# LAUNCHXL-F28069_B_1400922.net
KiCad netlist of a schematic drawn in EAGLE
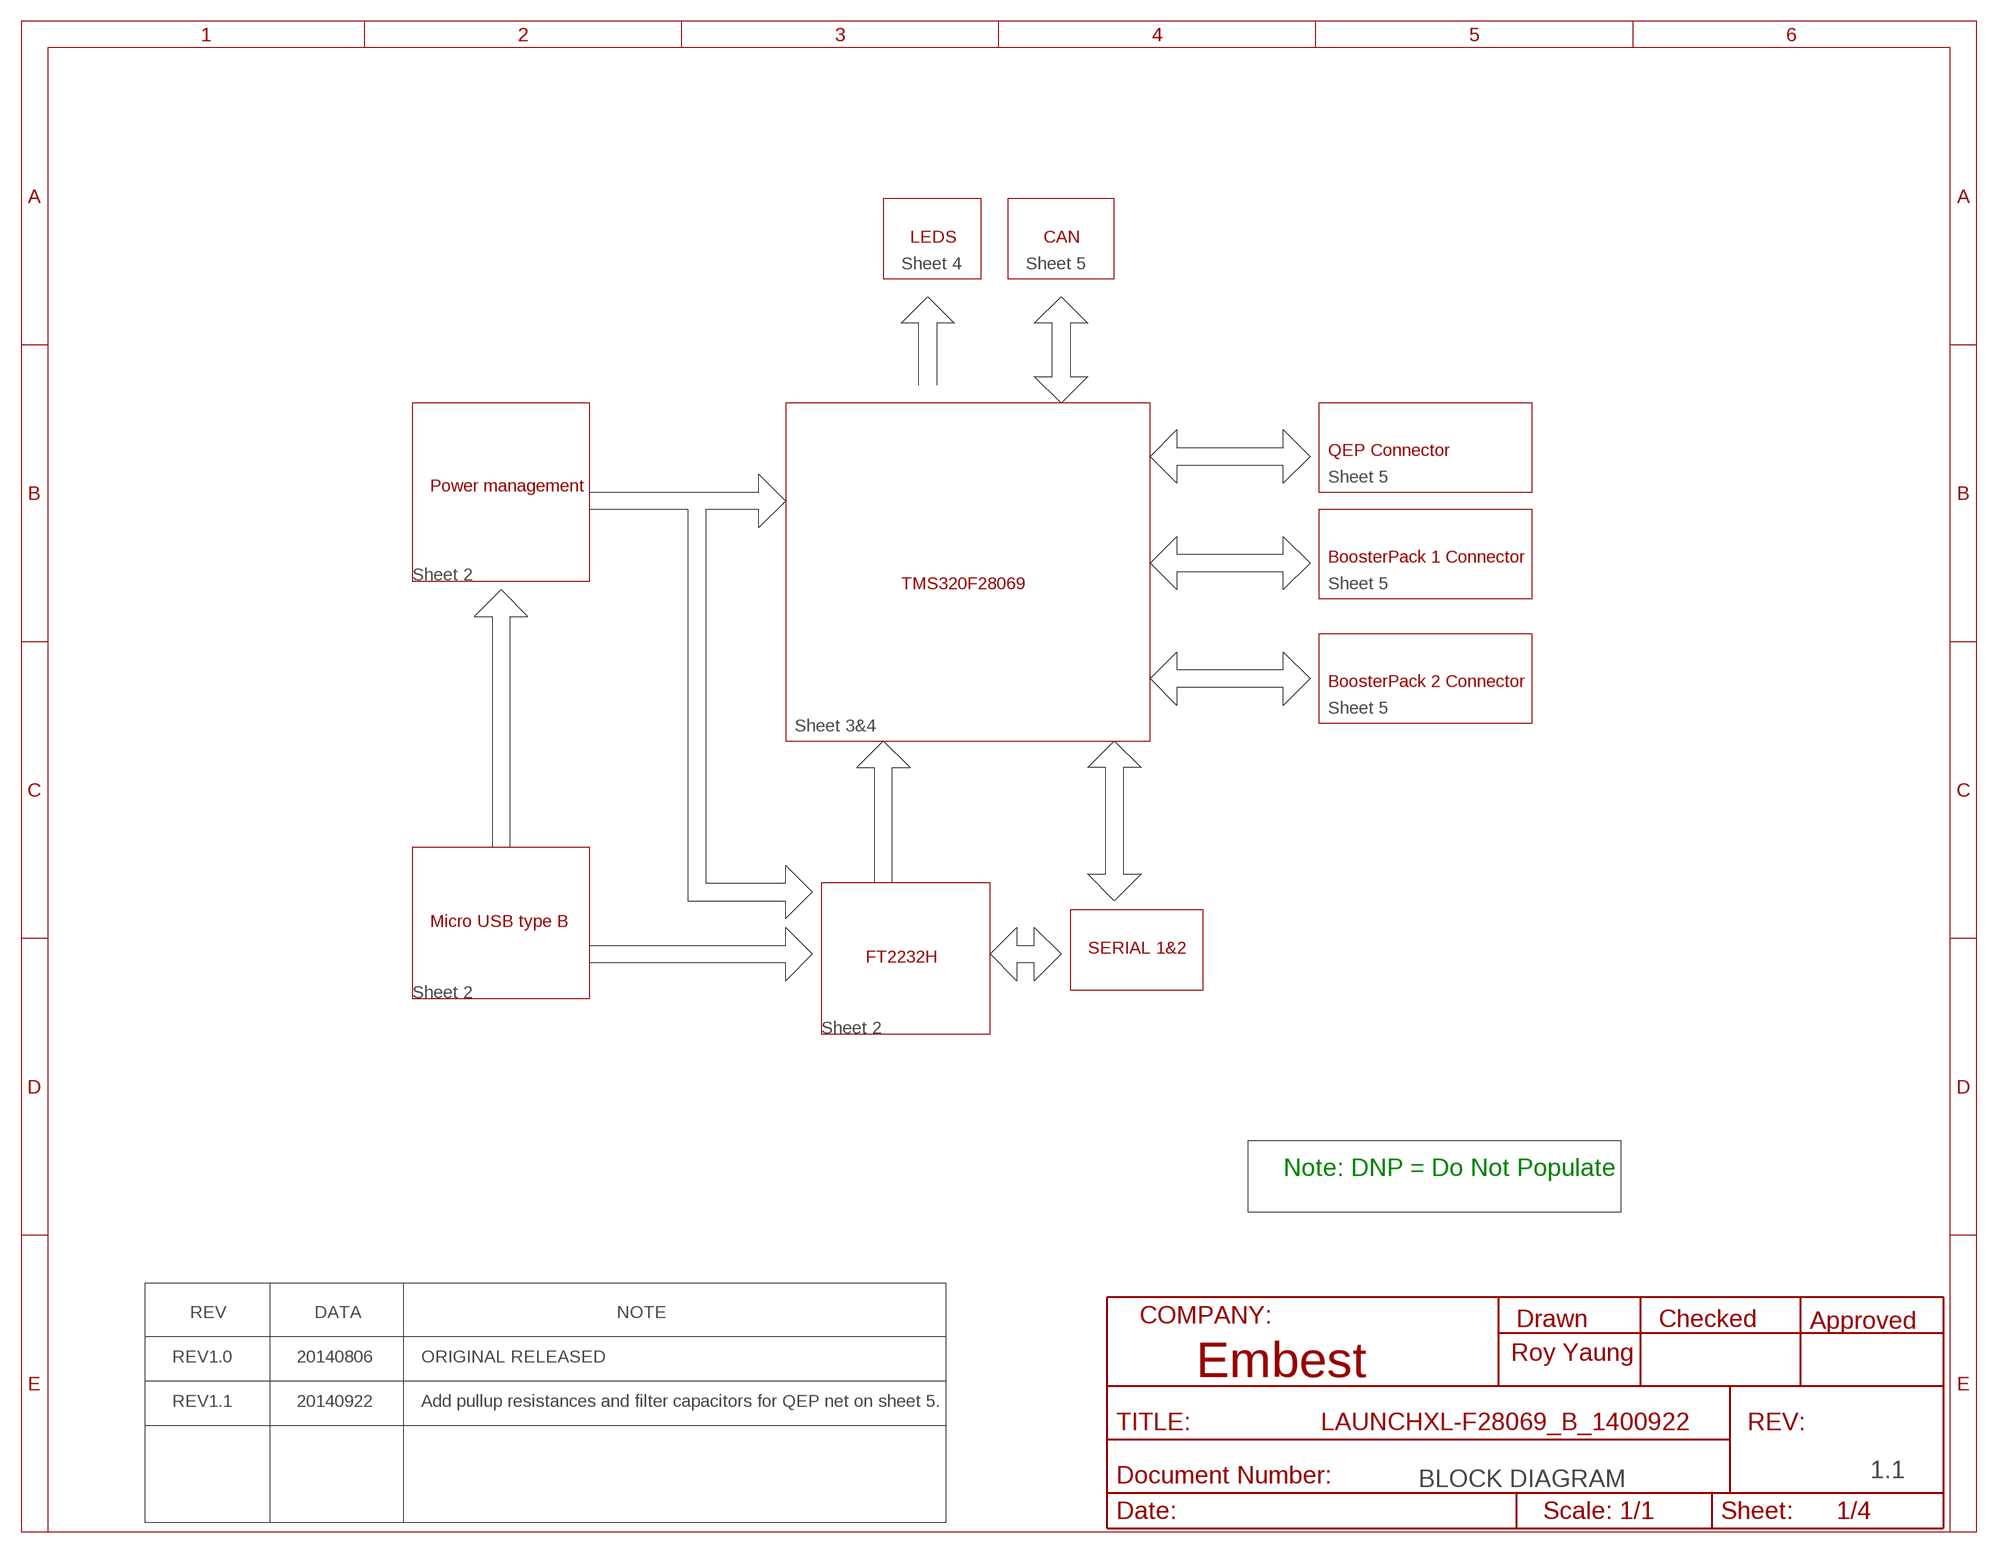
[diagram p0: schematic, sheet 1]
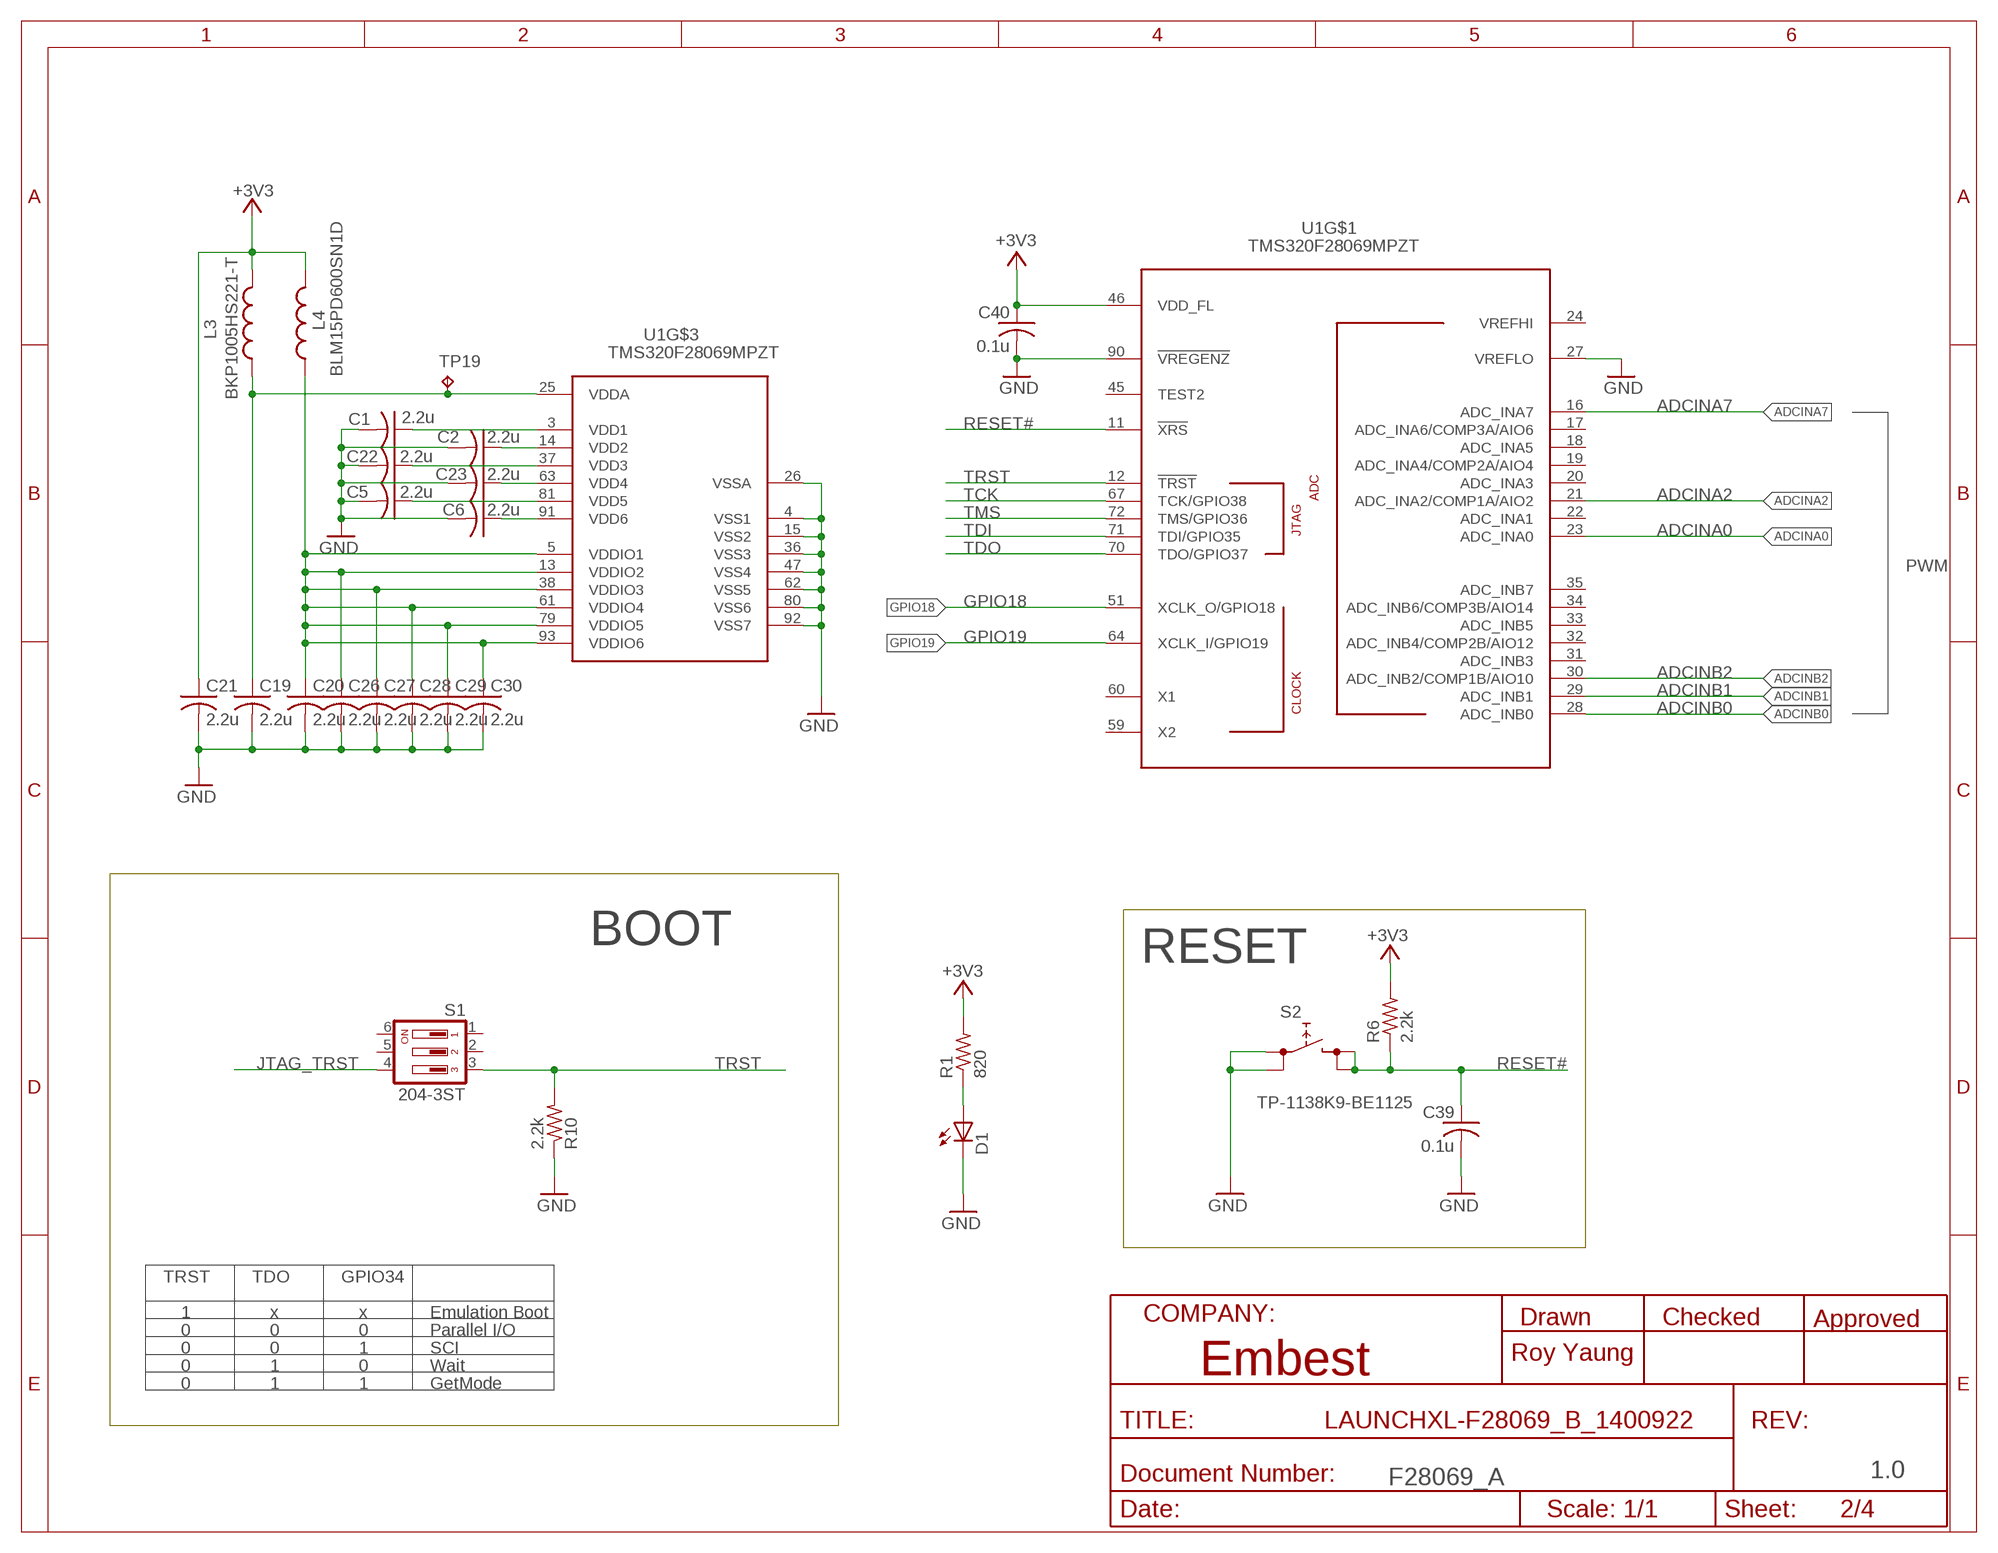
[diagram p1: schematic, sheet 2]
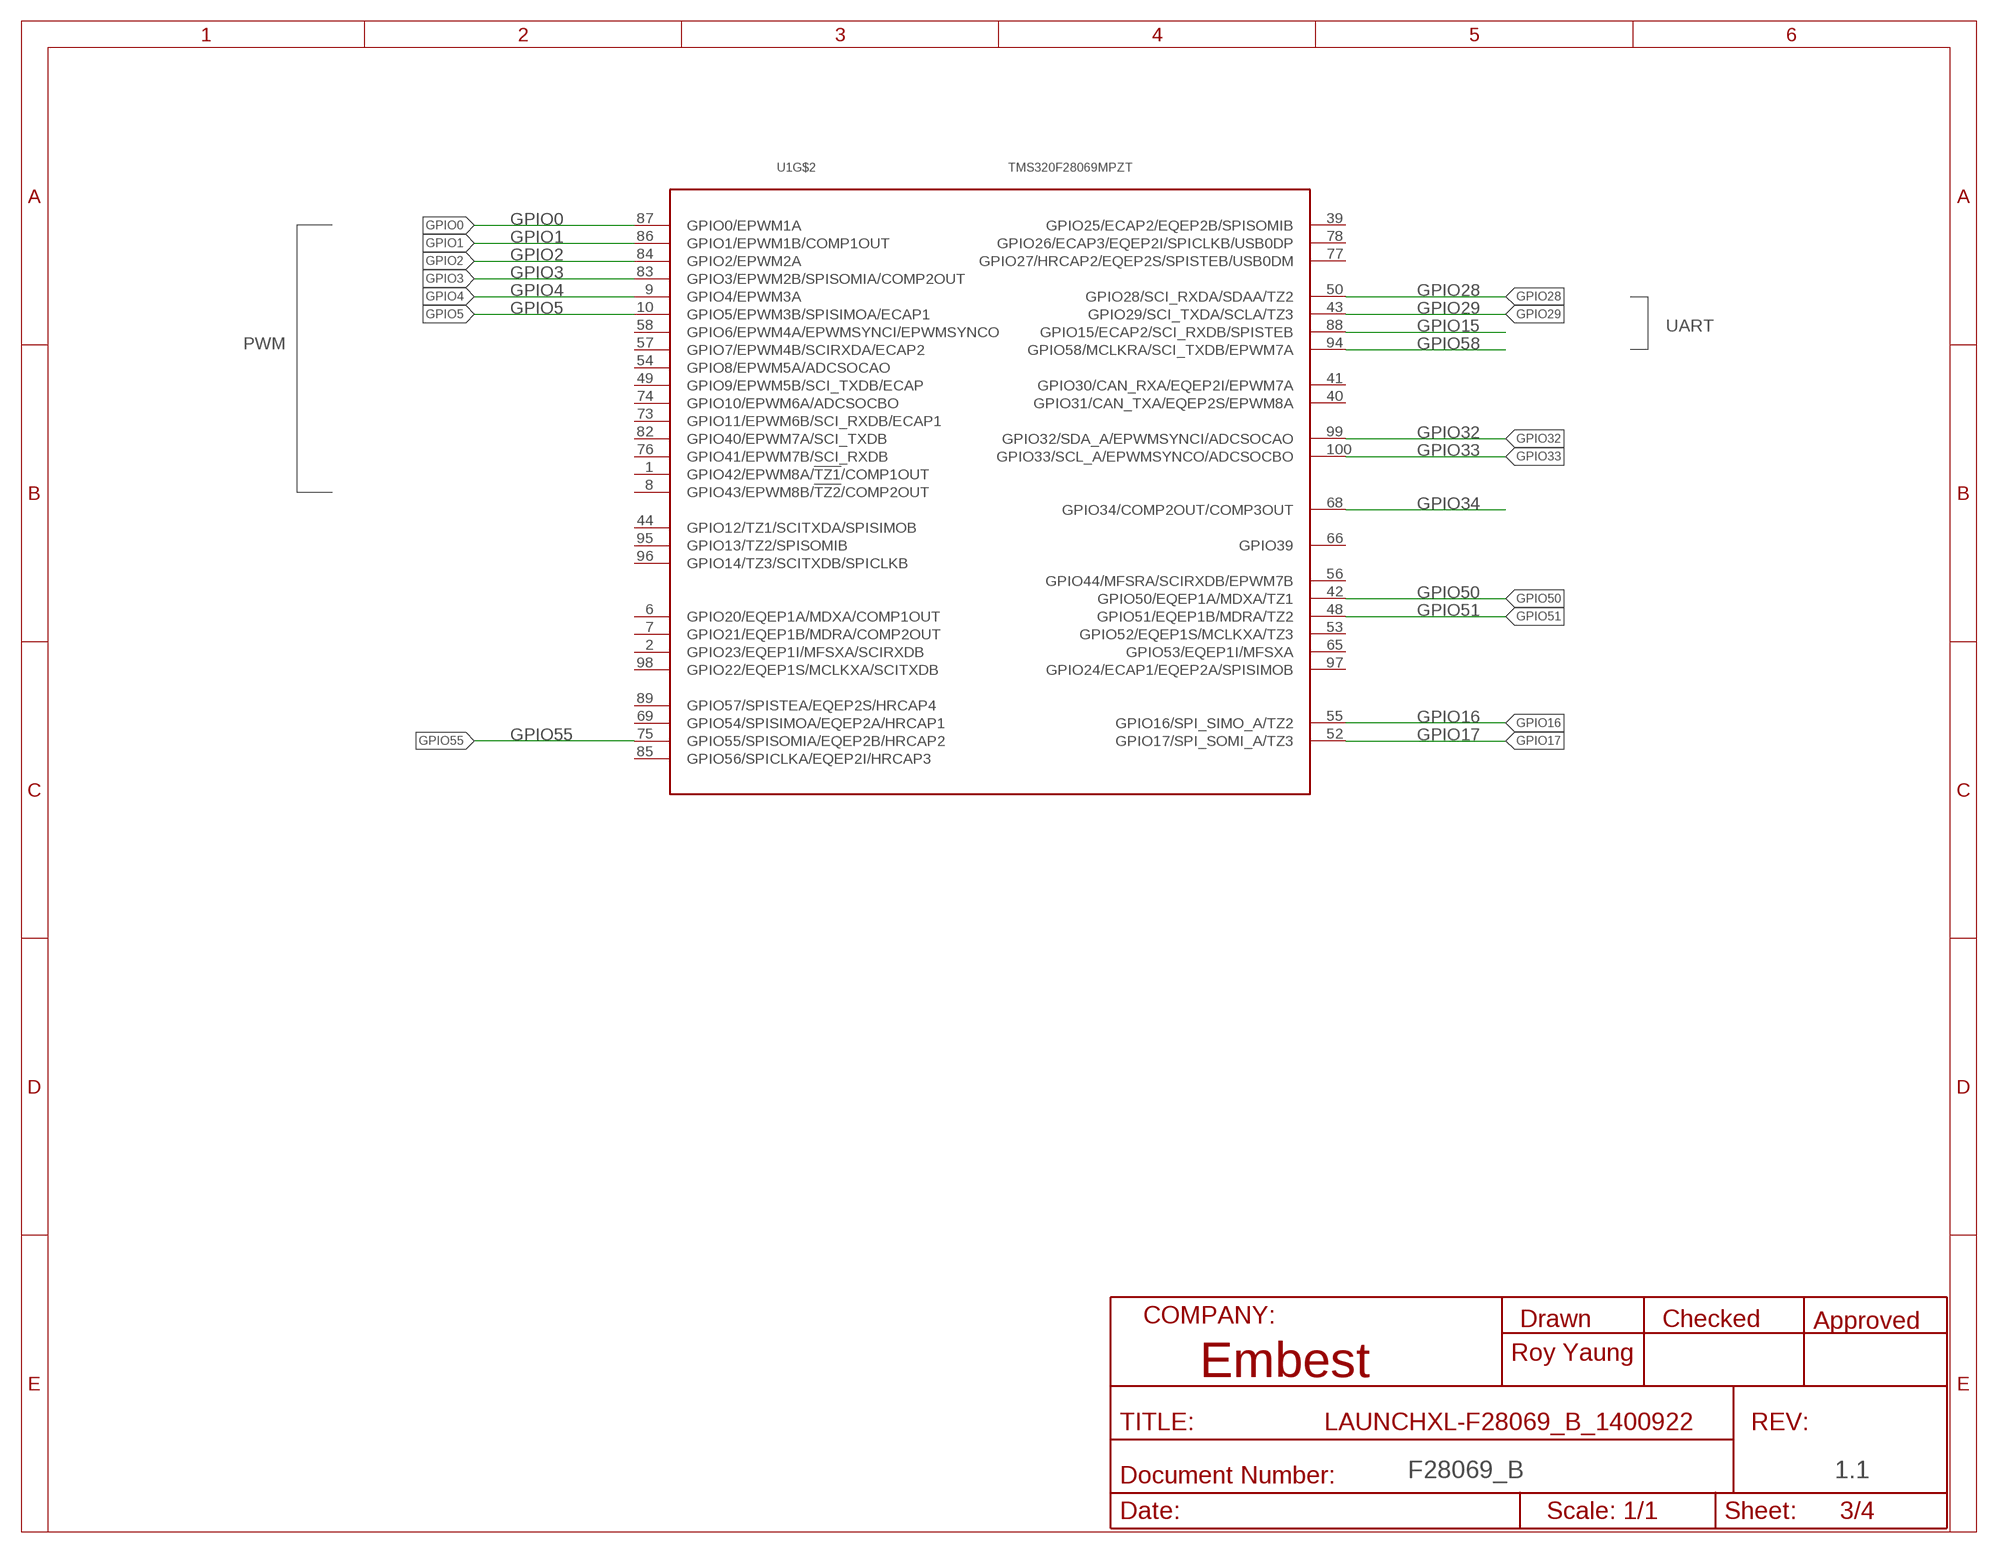
[diagram p2: schematic, sheet 3]
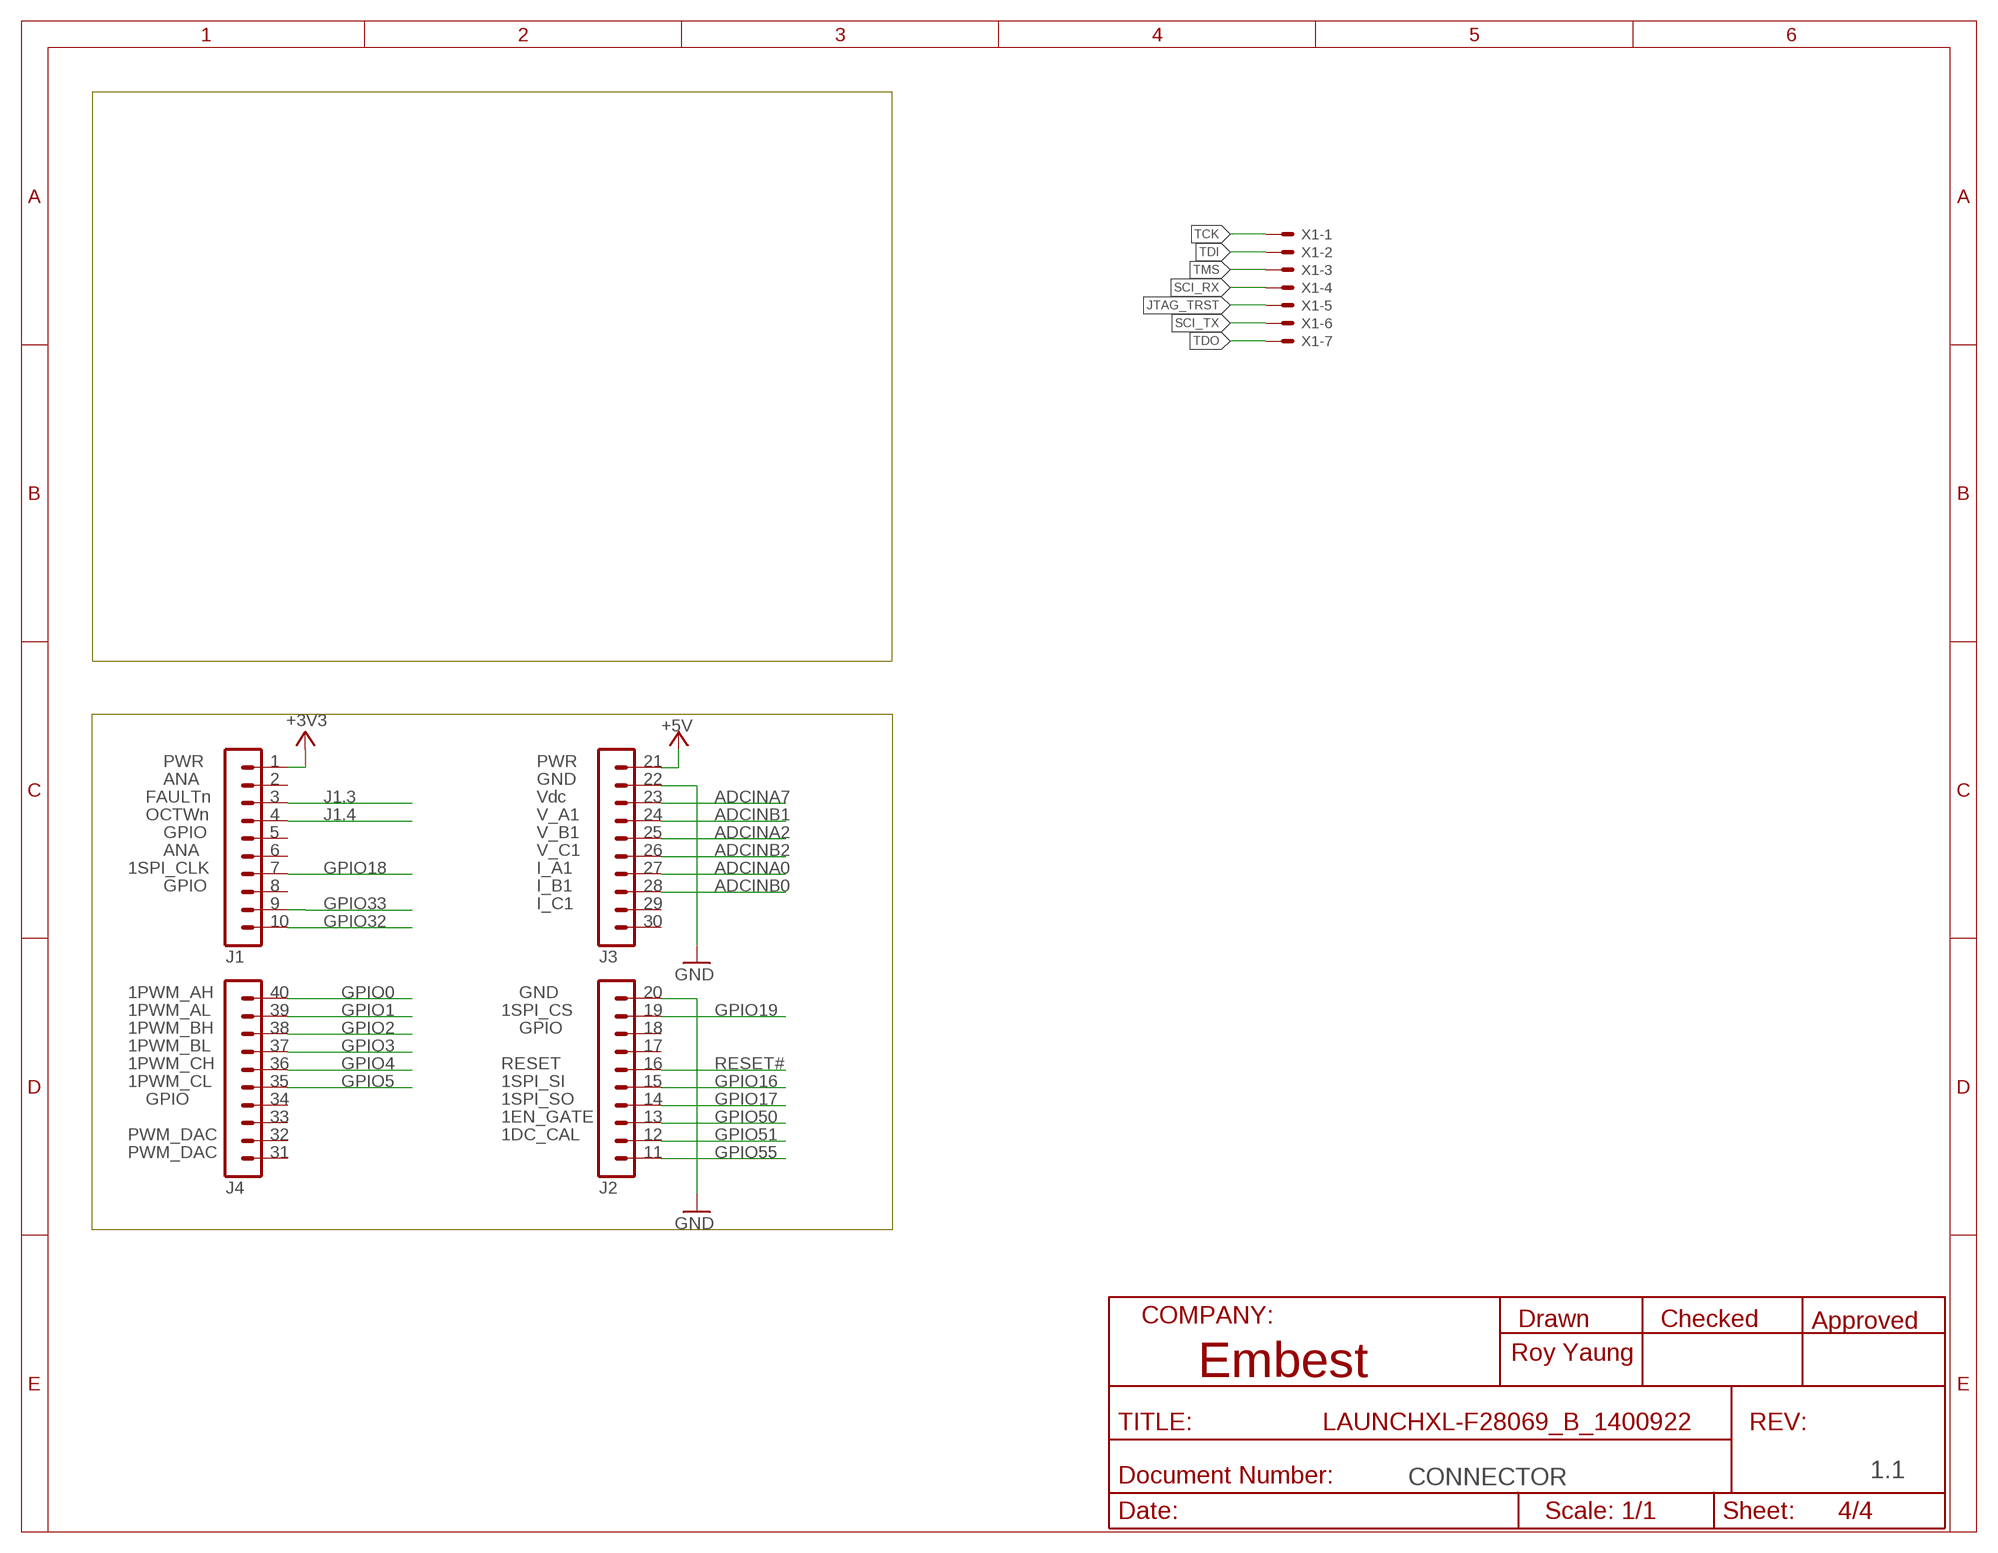
[diagram p3: schematic, sheet 4]

(export (version "E")
  (design (tool "Eeschema 10.0.6"))
  (components
    (comp (ref "C1")
      (value "2.2u")
      (footprint "eagle-import:C0402")
      (libsource (lib "eagle-import") (part "C-USC0402"))
    )
    (comp (ref "C2")
      (value "2.2u")
      (footprint "eagle-import:C0402")
      (libsource (lib "eagle-import") (part "C-USC0402"))
    )
    (comp (ref "C5")
      (value "2.2u")
      (footprint "eagle-import:C0402")
      (libsource (lib "eagle-import") (part "C-USC0402"))
    )
    (comp (ref "C6")
      (value "2.2u")
      (footprint "eagle-import:C0402")
      (libsource (lib "eagle-import") (part "C-USC0402"))
    )
    (comp (ref "C19")
      (value "2.2u")
      (footprint "eagle-import:C0402")
      (libsource (lib "eagle-import") (part "C-USC0402"))
    )
    (comp (ref "C20")
      (value "2.2u")
      (footprint "eagle-import:C0402")
      (libsource (lib "eagle-import") (part "C-USC0402"))
    )
    (comp (ref "C21")
      (value "2.2u")
      (footprint "eagle-import:C0402")
      (libsource (lib "eagle-import") (part "C-USC0402"))
    )
    (comp (ref "C22")
      (value "2.2u")
      (footprint "eagle-import:C0402")
      (libsource (lib "eagle-import") (part "C-USC0402"))
    )
    (comp (ref "C23")
      (value "2.2u")
      (footprint "eagle-import:C0402")
      (libsource (lib "eagle-import") (part "C-USC0402"))
    )
    (comp (ref "C26")
      (value "2.2u")
      (footprint "eagle-import:C0402")
      (libsource (lib "eagle-import") (part "C-USC0402"))
    )
    (comp (ref "C27")
      (value "2.2u")
      (footprint "eagle-import:C0402")
      (libsource (lib "eagle-import") (part "C-USC0402"))
    )
    (comp (ref "C28")
      (value "2.2u")
      (footprint "eagle-import:C0402")
      (libsource (lib "eagle-import") (part "C-USC0402"))
    )
    (comp (ref "C29")
      (value "2.2u")
      (footprint "eagle-import:C0402")
      (libsource (lib "eagle-import") (part "C-USC0402"))
    )
    (comp (ref "C30")
      (value "2.2u")
      (footprint "eagle-import:C0402")
      (libsource (lib "eagle-import") (part "C-USC0402"))
    )
    (comp (ref "C39")
      (value "0.1u")
      (footprint "eagle-import:C0402")
      (libsource (lib "eagle-import") (part "C-USC0402"))
    )
    (comp (ref "C40")
      (value "0.1u")
      (footprint "eagle-import:C0402")
      (libsource (lib "eagle-import") (part "C-USC0402"))
    )
    (comp (ref "D1")
      (value "LEDCHIP-LED0603")
      (footprint "eagle-import:CHIP-LED0603")
      (libsource (lib "eagle-import") (part "LEDCHIP-LED0603"))
    )
    (comp (ref "L3")
      (value "BKP1005HS221-T")
      (footprint "eagle-import:R0402")
      (libsource (lib "eagle-import") (part "L-US0402"))
    )
    (comp (ref "L4")
      (value "BLM15PD600SN1D")
      (footprint "eagle-import:R0402")
      (libsource (lib "eagle-import") (part "L-US0402"))
    )
    (comp (ref "R1")
      (value "820")
      (footprint "eagle-import:R0402")
      (libsource (lib "eagle-import") (part "R-US_R0402"))
    )
    (comp (ref "R6")
      (value "2.2k")
      (footprint "eagle-import:R0402")
      (libsource (lib "eagle-import") (part "R-US_R0402"))
    )
    (comp (ref "R10")
      (value "2.2k")
      (footprint "eagle-import:R0402")
      (libsource (lib "eagle-import") (part "R-US_R0402"))
    )
    (comp (ref "S1")
      (value "204-3ST")
      (footprint "eagle-import:CTS-219-03")
      (libsource (lib "eagle-import") (part "219-03"))
    )
    (comp (ref "S2")
      (value "TP-1138K9-BE1125")
      (footprint "eagle-import:FSMJSMA")
      (libsource (lib "eagle-import") (part "FSMJSMA"))
    )
    (comp (ref "TP19")
      (value "TESTPAD_TPB1,27")
      (footprint "eagle-import:TESTPAD_B1,27")
      (libsource (lib "eagle-import") (part "TESTPAD_TPB1,27"))
    )
    (comp (ref "U1")
      (value "TMS320F28069MPZT")
      (footprint "eagle-import:PQFP100")
      (libsource (lib "eagle-import") (part "TMS320F28069PZSR"))
    )
    (comp (ref "J1")
      (value "MA10-1")
      (footprint "eagle-import:MA10-1")
      (libsource (lib "eagle-import") (part "MA10-1"))
    )
    (comp (ref "J2")
      (value "MA10-1")
      (footprint "eagle-import:MA10-1")
      (libsource (lib "eagle-import") (part "MA10-1"))
    )
    (comp (ref "J3")
      (value "MA10-1")
      (footprint "eagle-import:MA10-1")
      (libsource (lib "eagle-import") (part "MA10-1"))
    )
    (comp (ref "J4")
      (value "MA10-1")
      (footprint "eagle-import:MA10-1")
      (libsource (lib "eagle-import") (part "MA10-1"))
    )
    (comp (ref "X1")
      (value "KK-156-7")
      (footprint "eagle-import:KK-156-7")
      (libsource (lib "eagle-import") (part "KK-156-7"))
    )
  )
  (nets
    (net (code "1") (name "+3V3") (class "Default")
      (node (ref "C21") (pin "1") (pinfunction "1_1") (pintype "passive"))
      (node (ref "C40") (pin "1") (pinfunction "1_1") (pintype "passive"))
      (node (ref "J1") (pin "1") (pinfunction "1_1") (pintype "passive"))
      (node (ref "L3") (pin "2") (pinfunction "2_2") (pintype "passive"))
      (node (ref "L4") (pin "2") (pinfunction "2_2") (pintype "passive"))
      (node (ref "R1") (pin "2") (pinfunction "2_2") (pintype "passive"))
      (node (ref "R6") (pin "2") (pinfunction "2_2") (pintype "passive"))
      (node (ref "U1") (pin "46") (pinfunction "VDD_FL_46") (pintype "power_in"))
    )
    (net (code "2") (name "+5V") (class "Default")
      (node (ref "J3") (pin "1") (pinfunction "1_1") (pintype "passive"))
    )
    (net (code "3") (name "ADCINA0") (class "Default")
      (node (ref "J3") (pin "7") (pinfunction "7_7") (pintype "passive"))
      (node (ref "U1") (pin "23") (pinfunction "ADC_INA0_23") (pintype "input"))
    )
    (net (code "4") (name "ADCINA2") (class "Default")
      (node (ref "J3") (pin "5") (pinfunction "5_5") (pintype "passive"))
      (node (ref "U1") (pin "21") (pinfunction "ADC_INA2/COMP1A/AIO2_21") (pintype "bidirectional"))
    )
    (net (code "5") (name "ADCINA7") (class "Default")
      (node (ref "J3") (pin "3") (pinfunction "3_3") (pintype "passive"))
      (node (ref "U1") (pin "16") (pinfunction "ADC_INA7_16") (pintype "input"))
    )
    (net (code "6") (name "ADCINB0") (class "Default")
      (node (ref "J3") (pin "8") (pinfunction "8_8") (pintype "passive"))
      (node (ref "U1") (pin "28") (pinfunction "ADC_INB0_28") (pintype "input"))
    )
    (net (code "7") (name "ADCINB1") (class "Default")
      (node (ref "J3") (pin "4") (pinfunction "4_4") (pintype "passive"))
      (node (ref "U1") (pin "29") (pinfunction "ADC_INB1_29") (pintype "input"))
    )
    (net (code "8") (name "ADCINB2") (class "Default")
      (node (ref "J3") (pin "6") (pinfunction "6_6") (pintype "passive"))
      (node (ref "U1") (pin "30") (pinfunction "ADC_INB2/COMP1B/AIO10_30") (pintype "bidirectional"))
    )
    (net (code "9") (name "GND") (class "Default")
      (node (ref "C1") (pin "2") (pinfunction "2_2") (pintype "passive"))
      (node (ref "C19") (pin "2") (pinfunction "2_2") (pintype "passive"))
      (node (ref "C2") (pin "2") (pinfunction "2_2") (pintype "passive"))
      (node (ref "C20") (pin "2") (pinfunction "2_2") (pintype "passive"))
      (node (ref "C21") (pin "2") (pinfunction "2_2") (pintype "passive"))
      (node (ref "C22") (pin "2") (pinfunction "2_2") (pintype "passive"))
      (node (ref "C23") (pin "2") (pinfunction "2_2") (pintype "passive"))
      (node (ref "C26") (pin "2") (pinfunction "2_2") (pintype "passive"))
      (node (ref "C27") (pin "2") (pinfunction "2_2") (pintype "passive"))
      (node (ref "C28") (pin "2") (pinfunction "2_2") (pintype "passive"))
      (node (ref "C29") (pin "2") (pinfunction "2_2") (pintype "passive"))
      (node (ref "C30") (pin "2") (pinfunction "2_2") (pintype "passive"))
      (node (ref "C39") (pin "2") (pinfunction "2_2") (pintype "passive"))
      (node (ref "C40") (pin "2") (pinfunction "2_2") (pintype "passive"))
      (node (ref "C5") (pin "2") (pinfunction "2_2") (pintype "passive"))
      (node (ref "C6") (pin "2") (pinfunction "2_2") (pintype "passive"))
      (node (ref "D1") (pin "C") (pinfunction "C_C") (pintype "passive"))
      (node (ref "J2") (pin "1") (pinfunction "1_1") (pintype "passive"))
      (node (ref "J3") (pin "2") (pinfunction "2_2") (pintype "passive"))
      (node (ref "R10") (pin "1") (pinfunction "1_1") (pintype "passive"))
      (node (ref "S2") (pin "P$1") (pinfunction "0_P$1") (pintype "passive"))
      (node (ref "S2") (pin "P$2") (pinfunction "0_P$2") (pintype "passive"))
      (node (ref "U1") (pin "15") (pinfunction "VSS2_15") (pintype "power_in"))
      (node (ref "U1") (pin "26") (pinfunction "VSSA_26") (pintype "power_in"))
      (node (ref "U1") (pin "27") (pinfunction "VREFLO_27") (pintype "input"))
      (node (ref "U1") (pin "36") (pinfunction "VSS3_36") (pintype "power_in"))
      (node (ref "U1") (pin "4") (pinfunction "VSS1_4") (pintype "power_in"))
      (node (ref "U1") (pin "47") (pinfunction "VSS4_47") (pintype "power_in"))
      (node (ref "U1") (pin "62") (pinfunction "VSS5_62") (pintype "power_in"))
      (node (ref "U1") (pin "80") (pinfunction "VSS6_80") (pintype "power_in"))
      (node (ref "U1") (pin "90") (pinfunction "~{VREGENZ}_90") (pintype "input"))
      (node (ref "U1") (pin "92") (pinfunction "VSS7_92") (pintype "power_in"))
    )
    (net (code "10") (name "GPIO0") (class "Default")
      (node (ref "J4") (pin "1") (pinfunction "1_1") (pintype "passive"))
      (node (ref "U1") (pin "87") (pinfunction "GPIO0/EPWM1A_87") (pintype "bidirectional"))
    )
    (net (code "11") (name "GPIO1") (class "Default")
      (node (ref "J4") (pin "2") (pinfunction "2_2") (pintype "passive"))
      (node (ref "U1") (pin "86") (pinfunction "GPIO1/EPWM1B/COMP1OUT_86") (pintype "bidirectional"))
    )
    (net (code "12") (name "GPIO2") (class "Default")
      (node (ref "J4") (pin "3") (pinfunction "3_3") (pintype "passive"))
      (node (ref "U1") (pin "84") (pinfunction "GPIO2/EPWM2A_84") (pintype "bidirectional"))
    )
    (net (code "13") (name "GPIO3") (class "Default")
      (node (ref "J4") (pin "4") (pinfunction "4_4") (pintype "passive"))
      (node (ref "U1") (pin "83") (pinfunction "GPIO3/EPWM2B/SPISOMIA/COMP2OUT_83") (pintype "bidirectional"))
    )
    (net (code "14") (name "GPIO4") (class "Default")
      (node (ref "J4") (pin "5") (pinfunction "5_5") (pintype "passive"))
      (node (ref "U1") (pin "9") (pinfunction "GPIO4/EPWM3A_9") (pintype "bidirectional"))
    )
    (net (code "15") (name "GPIO5") (class "Default")
      (node (ref "J4") (pin "6") (pinfunction "6_6") (pintype "passive"))
      (node (ref "U1") (pin "10") (pinfunction "GPIO5/EPWM3B/SPISIMOA/ECAP1_10") (pintype "bidirectional"))
    )
    (net (code "16") (name "GPIO15") (class "Default")
      (node (ref "U1") (pin "88") (pinfunction "GPIO15/ECAP2/SCI_RXDB/SPISTEB_88") (pintype "bidirectional"))
    )
    (net (code "17") (name "GPIO16") (class "Default")
      (node (ref "J2") (pin "6") (pinfunction "6_6") (pintype "passive"))
      (node (ref "U1") (pin "55") (pinfunction "GPIO16/SPI_SIMO_A/TZ2_55") (pintype "bidirectional"))
    )
    (net (code "18") (name "GPIO17") (class "Default")
      (node (ref "J2") (pin "7") (pinfunction "7_7") (pintype "passive"))
      (node (ref "U1") (pin "52") (pinfunction "GPIO17/SPI_SOMI_A/TZ3_52") (pintype "bidirectional"))
    )
    (net (code "19") (name "GPIO18") (class "Default")
      (node (ref "J1") (pin "7") (pinfunction "7_7") (pintype "passive"))
      (node (ref "U1") (pin "51") (pinfunction "XCLK_O/GPIO18_51") (pintype "output"))
    )
    (net (code "20") (name "GPIO19") (class "Default")
      (node (ref "J2") (pin "2") (pinfunction "2_2") (pintype "passive"))
      (node (ref "U1") (pin "64") (pinfunction "XCLK_I/GPIO19_64") (pintype "input"))
    )
    (net (code "21") (name "GPIO28") (class "Default")
      (node (ref "U1") (pin "50") (pinfunction "GPIO28/SCI_RXDA/SDAA/TZ2_50") (pintype "bidirectional"))
    )
    (net (code "22") (name "GPIO29") (class "Default")
      (node (ref "U1") (pin "43") (pinfunction "GPIO29/SCI_TXDA/SCLA/TZ3_43") (pintype "bidirectional"))
    )
    (net (code "23") (name "GPIO32") (class "Default")
      (node (ref "J1") (pin "10") (pinfunction "10_10") (pintype "passive"))
      (node (ref "U1") (pin "99") (pinfunction "GPIO32/SDA_A/EPWMSYNCI/ADCSOCAO_99") (pintype "bidirectional"))
    )
    (net (code "24") (name "GPIO33") (class "Default")
      (node (ref "J1") (pin "9") (pinfunction "9_9") (pintype "passive"))
      (node (ref "U1") (pin "100") (pinfunction "GPIO33/SCL_A/EPWMSYNCO/ADCSOCBO_100") (pintype "bidirectional"))
    )
    (net (code "25") (name "GPIO34") (class "Default")
      (node (ref "U1") (pin "68") (pinfunction "GPIO34/COMP2OUT/COMP3OUT_68") (pintype "bidirectional"))
    )
    (net (code "26") (name "GPIO50") (class "Default")
      (node (ref "J2") (pin "8") (pinfunction "8_8") (pintype "passive"))
      (node (ref "U1") (pin "42") (pinfunction "GPIO50/EQEP1A/MDXA/TZ1_42") (pintype "bidirectional"))
    )
    (net (code "27") (name "GPIO51") (class "Default")
      (node (ref "J2") (pin "9") (pinfunction "9_9") (pintype "passive"))
      (node (ref "U1") (pin "48") (pinfunction "GPIO51/EQEP1B/MDRA/TZ2_48") (pintype "bidirectional"))
    )
    (net (code "28") (name "GPIO55") (class "Default")
      (node (ref "J2") (pin "10") (pinfunction "10_10") (pintype "passive"))
      (node (ref "U1") (pin "75") (pinfunction "GPIO55/SPISOMIA/EQEP2B/HRCAP2_75") (pintype "bidirectional"))
    )
    (net (code "29") (name "GPIO58") (class "Default")
      (node (ref "U1") (pin "94") (pinfunction "GPIO58/MCLKRA/SCI_TXDB/EPWM7A_94") (pintype "bidirectional"))
    )
    (net (code "30") (name "J1.3") (class "Default")
      (node (ref "J1") (pin "3") (pinfunction "3_3") (pintype "passive"))
    )
    (net (code "31") (name "J1.4") (class "Default")
      (node (ref "J1") (pin "4") (pinfunction "4_4") (pintype "passive"))
    )
    (net (code "32") (name "JTAG_TRST") (class "Default")
      (node (ref "S1") (pin "4") (pinfunction "4_4") (pintype "passive"))
      (node (ref "X1") (pin "5") (pinfunction "S_5") (pintype "passive"))
    )
    (net (code "33") (name "Net-(D1-PadA)") (class "Default")
      (node (ref "D1") (pin "A") (pinfunction "A_A") (pintype "passive"))
      (node (ref "R1") (pin "1") (pinfunction "1_1") (pintype "passive"))
    )
    (net (code "34") (name "Net-(U1C-VDD1)") (class "Default")
      (node (ref "C1") (pin "1") (pinfunction "1_1") (pintype "passive"))
      (node (ref "U1") (pin "3") (pinfunction "VDD1_3") (pintype "power_in"))
    )
    (net (code "35") (name "Net-(U1C-VDD2)") (class "Default")
      (node (ref "C2") (pin "1") (pinfunction "1_1") (pintype "passive"))
      (node (ref "U1") (pin "14") (pinfunction "VDD2_14") (pintype "power_in"))
    )
    (net (code "36") (name "Net-(U1C-VDD3)") (class "Default")
      (node (ref "C22") (pin "1") (pinfunction "1_1") (pintype "passive"))
      (node (ref "U1") (pin "37") (pinfunction "VDD3_37") (pintype "power_in"))
    )
    (net (code "37") (name "Net-(U1C-VDD4)") (class "Default")
      (node (ref "C23") (pin "1") (pinfunction "1_1") (pintype "passive"))
      (node (ref "U1") (pin "63") (pinfunction "VDD4_63") (pintype "power_in"))
    )
    (net (code "38") (name "Net-(U1C-VDD5)") (class "Default")
      (node (ref "C5") (pin "1") (pinfunction "1_1") (pintype "passive"))
      (node (ref "U1") (pin "81") (pinfunction "VDD5_81") (pintype "power_in"))
    )
    (net (code "39") (name "Net-(U1C-VDD6)") (class "Default")
      (node (ref "C6") (pin "1") (pinfunction "1_1") (pintype "passive"))
      (node (ref "U1") (pin "91") (pinfunction "VDD6_91") (pintype "power_in"))
    )
    (net (code "40") (name "Net-(U1C-VDDA)") (class "Default")
      (node (ref "C19") (pin "1") (pinfunction "1_1") (pintype "passive"))
      (node (ref "L3") (pin "1") (pinfunction "1_1") (pintype "passive"))
      (node (ref "TP19") (pin "TP") (pinfunction "TP_TP") (pintype "input"))
      (node (ref "U1") (pin "25") (pinfunction "VDDA_25") (pintype "power_in"))
    )
    (net (code "41") (name "Net-(U1C-VDDIO1)") (class "Default")
      (node (ref "C20") (pin "1") (pinfunction "1_1") (pintype "passive"))
      (node (ref "C26") (pin "1") (pinfunction "1_1") (pintype "passive"))
      (node (ref "C27") (pin "1") (pinfunction "1_1") (pintype "passive"))
      (node (ref "C28") (pin "1") (pinfunction "1_1") (pintype "passive"))
      (node (ref "C29") (pin "1") (pinfunction "1_1") (pintype "passive"))
      (node (ref "C30") (pin "1") (pinfunction "1_1") (pintype "passive"))
      (node (ref "L4") (pin "1") (pinfunction "1_1") (pintype "passive"))
      (node (ref "U1") (pin "13") (pinfunction "VDDIO2_13") (pintype "power_in"))
      (node (ref "U1") (pin "38") (pinfunction "VDDIO3_38") (pintype "power_in"))
      (node (ref "U1") (pin "5") (pinfunction "VDDIO1_5") (pintype "power_in"))
      (node (ref "U1") (pin "61") (pinfunction "VDDIO4_61") (pintype "power_in"))
      (node (ref "U1") (pin "79") (pinfunction "VDDIO5_79") (pintype "power_in"))
      (node (ref "U1") (pin "93") (pinfunction "VDDIO6_93") (pintype "power_in"))
    )
    (net (code "42") (name "RESET#") (class "Default")
      (node (ref "C39") (pin "1") (pinfunction "1_1") (pintype "passive"))
      (node (ref "J2") (pin "5") (pinfunction "5_5") (pintype "passive"))
      (node (ref "R6") (pin "1") (pinfunction "1_1") (pintype "passive"))
      (node (ref "S2") (pin "P$3") (pinfunction "1_P$3") (pintype "passive"))
      (node (ref "S2") (pin "P$4") (pinfunction "1_P$4") (pintype "passive"))
      (node (ref "U1") (pin "11") (pinfunction "~{XRS}_11") (pintype "bidirectional"))
    )
    (net (code "43") (name "SCI_RX") (class "Default")
      (node (ref "X1") (pin "4") (pinfunction "S_4") (pintype "passive"))
    )
    (net (code "44") (name "SCI_TX") (class "Default")
      (node (ref "X1") (pin "6") (pinfunction "S_6") (pintype "passive"))
    )
    (net (code "45") (name "TCK") (class "Default")
      (node (ref "U1") (pin "67") (pinfunction "TCK/GPIO38_67") (pintype "input"))
      (node (ref "X1") (pin "1") (pinfunction "S_1") (pintype "passive"))
    )
    (net (code "46") (name "TDI") (class "Default")
      (node (ref "U1") (pin "71") (pinfunction "TDI/GPIO35_71") (pintype "input"))
      (node (ref "X1") (pin "2") (pinfunction "S_2") (pintype "passive"))
    )
    (net (code "47") (name "TDO") (class "Default")
      (node (ref "U1") (pin "70") (pinfunction "TDO/GPIO37_70") (pintype "output"))
      (node (ref "X1") (pin "7") (pinfunction "S_7") (pintype "passive"))
    )
    (net (code "48") (name "TMS") (class "Default")
      (node (ref "U1") (pin "72") (pinfunction "TMS/GPIO36_72") (pintype "input"))
      (node (ref "X1") (pin "3") (pinfunction "S_3") (pintype "passive"))
    )
    (net (code "49") (name "TRST") (class "Default")
      (node (ref "R10") (pin "2") (pinfunction "2_2") (pintype "passive"))
      (node (ref "S1") (pin "3") (pinfunction "3_3") (pintype "passive"))
      (node (ref "U1") (pin "12") (pinfunction "~{TRST}_12") (pintype "input"))
    )
    (net (code "50") (name "unconnected-(J1-Pad2)") (class "Default")
      (node (ref "J1") (pin "2") (pinfunction "2_2") (pintype "passive"))
    )
    (net (code "51") (name "unconnected-(J1-Pad5)") (class "Default")
      (node (ref "J1") (pin "5") (pinfunction "5_5") (pintype "passive"))
    )
    (net (code "52") (name "unconnected-(J1-Pad6)") (class "Default")
      (node (ref "J1") (pin "6") (pinfunction "6_6") (pintype "passive"))
    )
    (net (code "53") (name "unconnected-(J1-Pad8)") (class "Default")
      (node (ref "J1") (pin "8") (pinfunction "8_8") (pintype "passive"))
    )
    (net (code "54") (name "unconnected-(J2-Pad3)") (class "Default")
      (node (ref "J2") (pin "3") (pinfunction "3_3") (pintype "passive"))
    )
    (net (code "55") (name "unconnected-(J2-Pad4)") (class "Default")
      (node (ref "J2") (pin "4") (pinfunction "4_4") (pintype "passive"))
    )
    (net (code "56") (name "unconnected-(J3-Pad9)") (class "Default")
      (node (ref "J3") (pin "9") (pinfunction "9_9") (pintype "passive"))
    )
    (net (code "57") (name "unconnected-(J3-Pad10)") (class "Default")
      (node (ref "J3") (pin "10") (pinfunction "10_10") (pintype "passive"))
    )
    (net (code "58") (name "unconnected-(J4-Pad7)") (class "Default")
      (node (ref "J4") (pin "7") (pinfunction "7_7") (pintype "passive"))
    )
    (net (code "59") (name "unconnected-(J4-Pad8)") (class "Default")
      (node (ref "J4") (pin "8") (pinfunction "8_8") (pintype "passive"))
    )
    (net (code "60") (name "unconnected-(J4-Pad9)") (class "Default")
      (node (ref "J4") (pin "9") (pinfunction "9_9") (pintype "passive"))
    )
    (net (code "61") (name "unconnected-(J4-Pad10)") (class "Default")
      (node (ref "J4") (pin "10") (pinfunction "10_10") (pintype "passive"))
    )
    (net (code "62") (name "unconnected-(S1-Pad1)") (class "Default")
      (node (ref "S1") (pin "1") (pinfunction "1_1") (pintype "passive"))
    )
    (net (code "63") (name "unconnected-(S1-Pad2)") (class "Default")
      (node (ref "S1") (pin "2") (pinfunction "2_2") (pintype "passive"))
    )
    (net (code "64") (name "unconnected-(S1-Pad5)") (class "Default")
      (node (ref "S1") (pin "5") (pinfunction "5_5") (pintype "passive"))
    )
    (net (code "65") (name "unconnected-(S1-Pad6)") (class "Default")
      (node (ref "S1") (pin "6") (pinfunction "6_6") (pintype "passive"))
    )
    (net (code "66") (name "unconnected-(U1A-ADC_INA1-Pad22)") (class "Default")
      (node (ref "U1") (pin "22") (pinfunction "ADC_INA1_22") (pintype "input"))
    )
    (net (code "67") (name "unconnected-(U1A-ADC_INA3-Pad20)") (class "Default")
      (node (ref "U1") (pin "20") (pinfunction "ADC_INA3_20") (pintype "input"))
    )
    (net (code "68") (name "unconnected-(U1A-ADC_INA4{slash}COMP2A{slash}AIO4-Pad19)") (class "Default")
      (node (ref "U1") (pin "19") (pinfunction "ADC_INA4/COMP2A/AIO4_19") (pintype "bidirectional"))
    )
    (net (code "69") (name "unconnected-(U1A-ADC_INA5-Pad18)") (class "Default")
      (node (ref "U1") (pin "18") (pinfunction "ADC_INA5_18") (pintype "input"))
    )
    (net (code "70") (name "unconnected-(U1A-ADC_INA6{slash}COMP3A{slash}AIO6-Pad17)") (class "Default")
      (node (ref "U1") (pin "17") (pinfunction "ADC_INA6/COMP3A/AIO6_17") (pintype "bidirectional"))
    )
    (net (code "71") (name "unconnected-(U1A-ADC_INB3-Pad31)") (class "Default")
      (node (ref "U1") (pin "31") (pinfunction "ADC_INB3_31") (pintype "input"))
    )
    (net (code "72") (name "unconnected-(U1A-ADC_INB4{slash}COMP2B{slash}AIO12-Pad32)") (class "Default")
      (node (ref "U1") (pin "32") (pinfunction "ADC_INB4/COMP2B/AIO12_32") (pintype "bidirectional"))
    )
    (net (code "73") (name "unconnected-(U1A-ADC_INB5-Pad33)") (class "Default")
      (node (ref "U1") (pin "33") (pinfunction "ADC_INB5_33") (pintype "input"))
    )
    (net (code "74") (name "unconnected-(U1A-ADC_INB6{slash}COMP3B{slash}AIO14-Pad34)") (class "Default")
      (node (ref "U1") (pin "34") (pinfunction "ADC_INB6/COMP3B/AIO14_34") (pintype "bidirectional"))
    )
    (net (code "75") (name "unconnected-(U1A-ADC_INB7-Pad35)") (class "Default")
      (node (ref "U1") (pin "35") (pinfunction "ADC_INB7_35") (pintype "input"))
    )
    (net (code "76") (name "unconnected-(U1A-TEST2-Pad45)") (class "Default")
      (node (ref "U1") (pin "45") (pinfunction "TEST2_45") (pintype "output"))
    )
    (net (code "77") (name "unconnected-(U1A-VREFHI-Pad24)") (class "Default")
      (node (ref "U1") (pin "24") (pinfunction "VREFHI_24") (pintype "input"))
    )
    (net (code "78") (name "unconnected-(U1A-X1-Pad60)") (class "Default")
      (node (ref "U1") (pin "60") (pinfunction "X1_60") (pintype "input"))
    )
    (net (code "79") (name "unconnected-(U1A-X2-Pad59)") (class "Default")
      (node (ref "U1") (pin "59") (pinfunction "X2_59") (pintype "output"))
    )
    (net (code "80") (name "unconnected-(U1B-GPIO6{slash}EPWM4A{slash}EPWMSYNCI{slash}EPWMSYNCO-Pad58)") (class "Default")
      (node (ref "U1") (pin "58") (pinfunction "GPIO6/EPWM4A/EPWMSYNCI/EPWMSYNCO_58") (pintype "bidirectional"))
    )
    (net (code "81") (name "unconnected-(U1B-GPIO7{slash}EPWM4B{slash}SCIRXDA{slash}ECAP2-Pad57)") (class "Default")
      (node (ref "U1") (pin "57") (pinfunction "GPIO7/EPWM4B/SCIRXDA/ECAP2_57") (pintype "bidirectional"))
    )
    (net (code "82") (name "unconnected-(U1B-GPIO8{slash}EPWM5A{slash}ADCSOCAO-Pad54)") (class "Default")
      (node (ref "U1") (pin "54") (pinfunction "GPIO8/EPWM5A/ADCSOCAO_54") (pintype "bidirectional"))
    )
    (net (code "83") (name "unconnected-(U1B-GPIO9{slash}EPWM5B{slash}SCI_TXDB{slash}ECAP-Pad49)") (class "Default")
      (node (ref "U1") (pin "49") (pinfunction "GPIO9/EPWM5B/SCI_TXDB/ECAP_49") (pintype "bidirectional"))
    )
    (net (code "84") (name "unconnected-(U1B-GPIO10{slash}EPWM6A{slash}ADCSOCBO-Pad74)") (class "Default")
      (node (ref "U1") (pin "74") (pinfunction "GPIO10/EPWM6A/ADCSOCBO_74") (pintype "bidirectional"))
    )
    (net (code "85") (name "unconnected-(U1B-GPIO11{slash}EPWM6B{slash}SCI_RXDB{slash}ECAP1-Pad73)") (class "Default")
      (node (ref "U1") (pin "73") (pinfunction "GPIO11/EPWM6B/SCI_RXDB/ECAP1_73") (pintype "bidirectional"))
    )
    (net (code "86") (name "unconnected-(U1B-GPIO12{slash}TZ1{slash}SCITXDA{slash}SPISIMOB-Pad44)") (class "Default")
      (node (ref "U1") (pin "44") (pinfunction "GPIO12/TZ1/SCITXDA/SPISIMOB_44") (pintype "bidirectional"))
    )
    (net (code "87") (name "unconnected-(U1B-GPIO13{slash}TZ2{slash}SPISOMIB-Pad95)") (class "Default")
      (node (ref "U1") (pin "95") (pinfunction "GPIO13/TZ2/SPISOMIB_95") (pintype "bidirectional"))
    )
    (net (code "88") (name "unconnected-(U1B-GPIO14{slash}TZ3{slash}SCITXDB{slash}SPICLKB-Pad96)") (class "Default")
      (node (ref "U1") (pin "96") (pinfunction "GPIO14/TZ3/SCITXDB/SPICLKB_96") (pintype "bidirectional"))
    )
    (net (code "89") (name "unconnected-(U1B-GPIO20{slash}EQEP1A{slash}MDXA{slash}COMP1OUT-Pad6)") (class "Default")
      (node (ref "U1") (pin "6") (pinfunction "GPIO20/EQEP1A/MDXA/COMP1OUT_6") (pintype "bidirectional"))
    )
    (net (code "90") (name "unconnected-(U1B-GPIO21{slash}EQEP1B{slash}MDRA{slash}COMP2OUT-Pad7)") (class "Default")
      (node (ref "U1") (pin "7") (pinfunction "GPIO21/EQEP1B/MDRA/COMP2OUT_7") (pintype "bidirectional"))
    )
    (net (code "91") (name "unconnected-(U1B-GPIO22{slash}EQEP1S{slash}MCLKXA{slash}SCITXDB-Pad98)") (class "Default")
      (node (ref "U1") (pin "98") (pinfunction "GPIO22/EQEP1S/MCLKXA/SCITXDB_98") (pintype "bidirectional"))
    )
    (net (code "92") (name "unconnected-(U1B-GPIO23{slash}EQEP1I{slash}MFSXA{slash}SCIRXDB-Pad2)") (class "Default")
      (node (ref "U1") (pin "2") (pinfunction "GPIO23/EQEP1I/MFSXA/SCIRXDB_2") (pintype "bidirectional"))
    )
    (net (code "93") (name "unconnected-(U1B-GPIO24{slash}ECAP1{slash}EQEP2A{slash}SPISIMOB-Pad97)") (class "Default")
      (node (ref "U1") (pin "97") (pinfunction "GPIO24/ECAP1/EQEP2A/SPISIMOB_97") (pintype "bidirectional"))
    )
    (net (code "94") (name "unconnected-(U1B-GPIO25{slash}ECAP2{slash}EQEP2B{slash}SPISOMIB-Pad39)") (class "Default")
      (node (ref "U1") (pin "39") (pinfunction "GPIO25/ECAP2/EQEP2B/SPISOMIB_39") (pintype "bidirectional"))
    )
    (net (code "95") (name "unconnected-(U1B-GPIO26{slash}ECAP3{slash}EQEP2I{slash}SPICLKB{slash}USB0DP-Pad78)") (class "Default")
      (node (ref "U1") (pin "78") (pinfunction "GPIO26/ECAP3/EQEP2I/SPICLKB/USB0DP_78") (pintype "bidirectional"))
    )
    (net (code "96") (name "unconnected-(U1B-GPIO27{slash}HRCAP2{slash}EQEP2S{slash}SPISTEB{slash}USB0DM-Pad77)") (class "Default")
      (node (ref "U1") (pin "77") (pinfunction "GPIO27/HRCAP2/EQEP2S/SPISTEB/USB0DM_77") (pintype "bidirectional"))
    )
    (net (code "97") (name "unconnected-(U1B-GPIO30{slash}CAN_RXA{slash}EQEP2I{slash}EPWM7A-Pad41)") (class "Default")
      (node (ref "U1") (pin "41") (pinfunction "GPIO30/CAN_RXA/EQEP2I/EPWM7A_41") (pintype "bidirectional"))
    )
    (net (code "98") (name "unconnected-(U1B-GPIO31{slash}CAN_TXA{slash}EQEP2S{slash}EPWM8A-Pad40)") (class "Default")
      (node (ref "U1") (pin "40") (pinfunction "GPIO31/CAN_TXA/EQEP2S/EPWM8A_40") (pintype "bidirectional"))
    )
    (net (code "99") (name "unconnected-(U1B-GPIO39-Pad66)") (class "Default")
      (node (ref "U1") (pin "66") (pinfunction "GPIO39_66") (pintype "bidirectional"))
    )
    (net (code "100") (name "unconnected-(U1B-GPIO40{slash}EPWM7A{slash}SCI_TXDB-Pad82)") (class "Default")
      (node (ref "U1") (pin "82") (pinfunction "GPIO40/EPWM7A/SCI_TXDB_82") (pintype "bidirectional"))
    )
    (net (code "101") (name "unconnected-(U1B-GPIO41{slash}EPWM7B{slash}SCI_RXDB-Pad76)") (class "Default")
      (node (ref "U1") (pin "76") (pinfunction "GPIO41/EPWM7B/SCI_RXDB_76") (pintype "bidirectional"))
    )
    (net (code "102") (name "unconnected-(U1B-GPIO42{slash}EPWM8A{slash}~{TZ1}{slash}COMP1OUT-Pad1)") (class "Default")
      (node (ref "U1") (pin "1") (pinfunction "GPIO42/EPWM8A/~{TZ1}/COMP1OUT_1") (pintype "bidirectional"))
    )
    (net (code "103") (name "unconnected-(U1B-GPIO43{slash}EPWM8B{slash}~{TZ2}{slash}COMP2OUT-Pad8)") (class "Default")
      (node (ref "U1") (pin "8") (pinfunction "GPIO43/EPWM8B/~{TZ2}/COMP2OUT_8") (pintype "bidirectional"))
    )
    (net (code "104") (name "unconnected-(U1B-GPIO44{slash}MFSRA{slash}SCIRXDB{slash}EPWM7B-Pad56)") (class "Default")
      (node (ref "U1") (pin "56") (pinfunction "GPIO44/MFSRA/SCIRXDB/EPWM7B_56") (pintype "bidirectional"))
    )
    (net (code "105") (name "unconnected-(U1B-GPIO52{slash}EQEP1S{slash}MCLKXA{slash}TZ3-Pad53)") (class "Default")
      (node (ref "U1") (pin "53") (pinfunction "GPIO52/EQEP1S/MCLKXA/TZ3_53") (pintype "bidirectional"))
    )
    (net (code "106") (name "unconnected-(U1B-GPIO53{slash}EQEP1I{slash}MFSXA-Pad65)") (class "Default")
      (node (ref "U1") (pin "65") (pinfunction "GPIO53/EQEP1I/MFSXA_65") (pintype "bidirectional"))
    )
    (net (code "107") (name "unconnected-(U1B-GPIO54{slash}SPISIMOA{slash}EQEP2A{slash}HRCAP1-Pad69)") (class "Default")
      (node (ref "U1") (pin "69") (pinfunction "GPIO54/SPISIMOA/EQEP2A/HRCAP1_69") (pintype "bidirectional"))
    )
    (net (code "108") (name "unconnected-(U1B-GPIO56{slash}SPICLKA{slash}EQEP2I{slash}HRCAP3-Pad85)") (class "Default")
      (node (ref "U1") (pin "85") (pinfunction "GPIO56/SPICLKA/EQEP2I/HRCAP3_85") (pintype "bidirectional"))
    )
    (net (code "109") (name "unconnected-(U1B-GPIO57{slash}SPISTEA{slash}EQEP2S{slash}HRCAP4-Pad89)") (class "Default")
      (node (ref "U1") (pin "89") (pinfunction "GPIO57/SPISTEA/EQEP2S/HRCAP4_89") (pintype "bidirectional"))
    )
  )
)
